# Drimp_Quadcopter.net
KiCad netlist of a schematic drawn in Altium Designer
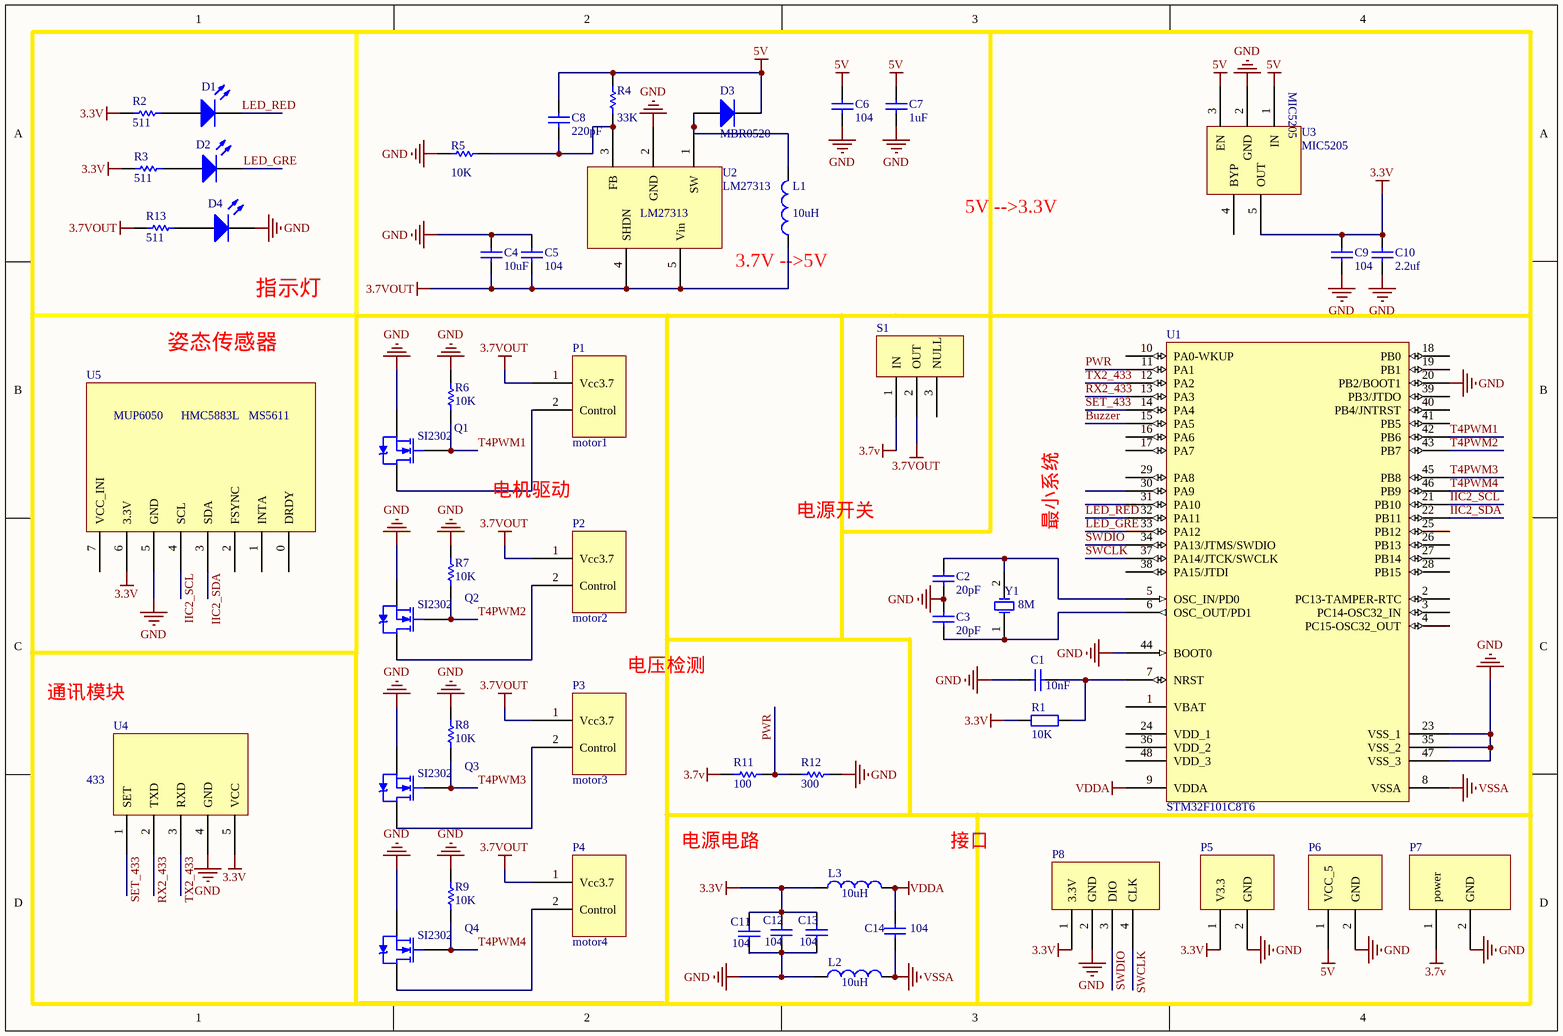
[diagram p0: Drimp_Quadcopter_升压部分未改变.SchDoc]

(export (version "E")
  (design (tool "Eeschema 10.0.6"))
  (components
    (comp (ref "C1")
      (value "10nF")
      (footprint "0603-N-CAP")
      (description "Capacitor")
      (fields (field (name "Comment") "Cap") (field (name "PUBLISHER") "Altium Limited"))
      (libsource (lib "Miscellaneous Devices") (part "Cap"))
    )
    (comp (ref "C2")
      (value "20pF")
      (footprint "0603-N-CAP")
      (description "Capacitor")
      (fields (field (name "Comment") "Cap") (field (name "PUBLISHER") "Altium Limited"))
      (libsource (lib "Miscellaneous Devices") (part "Cap"))
    )
    (comp (ref "C3")
      (value "20pF")
      (footprint "0603-N-CAP")
      (description "Capacitor")
      (fields (field (name "Comment") "Cap") (field (name "PUBLISHER") "Altium Limited"))
      (libsource (lib "Miscellaneous Devices") (part "Cap"))
    )
    (comp (ref "C4")
      (value "10uF")
      (footprint "0603-N-CAP")
      (description "Capacitor")
      (fields (field (name "Comment") "Cap") (field (name "PUBLISHER") "Altium Limited"))
      (libsource (lib "Miscellaneous Devices") (part "Cap"))
    )
    (comp (ref "C5")
      (value "104")
      (footprint "0603-N-CAP")
      (description "Capacitor")
      (fields (field (name "Comment") "Cap") (field (name "PUBLISHER") "Altium Limited"))
      (libsource (lib "Miscellaneous Devices") (part "Cap"))
    )
    (comp (ref "C6")
      (value "104")
      (footprint "0603-N-CAP")
      (description "Capacitor")
      (fields (field (name "Comment") "Cap") (field (name "PUBLISHER") "Altium Limited"))
      (libsource (lib "Miscellaneous Devices") (part "Cap"))
    )
    (comp (ref "C7")
      (value "1uF")
      (footprint "0603-N-CAP")
      (description "Capacitor")
      (fields (field (name "Comment") "Cap") (field (name "PUBLISHER") "Altium Limited"))
      (libsource (lib "Miscellaneous Devices") (part "Cap"))
    )
    (comp (ref "C8")
      (value "220pF")
      (footprint "0603-N-CAP")
      (description "Capacitor")
      (fields (field (name "Comment") "Cap") (field (name "PUBLISHER") "Altium Limited"))
      (libsource (lib "Miscellaneous Devices") (part "Cap"))
    )
    (comp (ref "C9")
      (value "104")
      (footprint "0603-N-CAP")
      (description "Capacitor")
      (fields (field (name "Comment") "Cap") (field (name "PUBLISHER") "Altium Limited"))
      (libsource (lib "Miscellaneous Devices") (part "Cap"))
    )
    (comp (ref "C10")
      (value "2.2uf")
      (footprint "0603-N-CAP")
      (description "Capacitor")
      (fields (field (name "Comment") "Cap") (field (name "PUBLISHER") "Altium Limited"))
      (libsource (lib "Miscellaneous Devices") (part "Cap"))
    )
    (comp (ref "C11")
      (value "104")
      (footprint "0603-N-CAP")
      (description "Capacitor")
      (fields (field (name "Comment") "Cap") (field (name "PUBLISHER") "Altium Limited"))
      (libsource (lib "Miscellaneous Devices") (part "Cap"))
    )
    (comp (ref "C12")
      (value "104")
      (footprint "0603-N-CAP")
      (description "Capacitor")
      (fields (field (name "Comment") "Cap") (field (name "PUBLISHER") "Altium Limited"))
      (libsource (lib "Miscellaneous Devices") (part "Cap"))
    )
    (comp (ref "C13")
      (value "104")
      (footprint "0603-N-CAP")
      (description "Capacitor")
      (fields (field (name "Comment") "Cap") (field (name "PUBLISHER") "Altium Limited"))
      (libsource (lib "Miscellaneous Devices") (part "Cap"))
    )
    (comp (ref "C14")
      (value "104")
      (footprint "0603-N-CAP")
      (description "Capacitor")
      (fields (field (name "Comment") "Cap") (field (name "PUBLISHER") "Altium Limited"))
      (libsource (lib "Miscellaneous Devices") (part "Cap"))
    )
    (comp (ref "D1")
      (value "D2")
      (footprint "6-0805_N")
      (description "Typical BLUE SiC LED")
      (fields (field (name "PUBLISHER") "Altium Limited"))
      (libsource (lib "Miscellaneous Devices") (part "LED3"))
    )
    (comp (ref "D2")
      (value "D2")
      (footprint "6-0805_N")
      (description "Typical BLUE SiC LED")
      (fields (field (name "PUBLISHER") "Altium Limited"))
      (libsource (lib "Miscellaneous Devices") (part "LED3"))
    )
    (comp (ref "D3")
      (value "MBR0520")
      (footprint "425")
      (description "Default Diode")
      (fields (field (name "PUBLISHER") "Altium Limited"))
      (libsource (lib "Miscellaneous Devices") (part "Diode"))
    )
    (comp (ref "D4")
      (value "D2")
      (footprint "6-0805_N")
      (description "Typical BLUE SiC LED")
      (fields (field (name "PUBLISHER") "Altium Limited"))
      (libsource (lib "Miscellaneous Devices") (part "LED3"))
    )
    (comp (ref "L1")
      (value "10uH")
      (footprint "0603-N - res")
      (description "Inductor")
      (fields (field (name "PUBLISHER") "Altium Limited"))
      (libsource (lib "Miscellaneous Devices") (part "Inductor"))
    )
    (comp (ref "L2")
      (value "10uH")
      (footprint "0603-N - res")
      (description "Inductor")
      (fields (field (name "PUBLISHER") "Altium Limited"))
      (libsource (lib "Miscellaneous Devices") (part "Inductor"))
    )
    (comp (ref "L3")
      (value "10uH")
      (footprint "0603-N - res")
      (description "Inductor")
      (fields (field (name "PUBLISHER") "Altium Limited"))
      (libsource (lib "Miscellaneous Devices") (part "Inductor"))
    )
    (comp (ref "P1")
      (value "motor1")
      (footprint "Motor")
      (description "电机连接口")
      (libsource (lib "Schlib1") (part "motor"))
    )
    (comp (ref "P2")
      (value "motor2")
      (footprint "Motor")
      (description "电机连接口")
      (libsource (lib "Schlib1") (part "motor"))
    )
    (comp (ref "P3")
      (value "motor3")
      (footprint "Motor")
      (description "电机连接口")
      (libsource (lib "Schlib1") (part "motor"))
    )
    (comp (ref "P4")
      (value "motor4")
      (footprint "Motor")
      (description "电机连接口")
      (libsource (lib "Schlib1") (part "motor"))
    )
    (comp (ref "P5") (value "3.3V_GND") (footprint "3.3V_GND") (libsource (lib "Schlib1") (part "3.3V_GND")))
    (comp (ref "P6") (value "5V_GND") (footprint "5V_GND") (libsource (lib "Schlib1") (part "5V_GND")))
    (comp (ref "P7")
      (value "Power_GND")
      (footprint "Power_GND")
      (libsource (lib "Schlib1") (part "Power_GND"))
    )
    (comp (ref "P8")
      (value "SW_download")
      (footprint "SW_download")
      (libsource (lib "Schlib1") (part "SW_download"))
    )
    (comp (ref "Q1")
      (value "SI2302")
      (footprint "SOT-23_M")
      (description "HEXFET Power MOSFET")
      (fields (field (name "PUBLISHER") "Altium Limited"))
      (libsource (lib "IR Discrete MOSFET - Power") (part "IRLML2402"))
    )
    (comp (ref "Q2")
      (value "SI2302")
      (footprint "SOT-23_M")
      (description "HEXFET Power MOSFET")
      (fields (field (name "PUBLISHER") "Altium Limited"))
      (libsource (lib "IR Discrete MOSFET - Power") (part "IRLML2402"))
    )
    (comp (ref "Q3")
      (value "SI2302")
      (footprint "SOT-23_M")
      (description "HEXFET Power MOSFET")
      (fields (field (name "PUBLISHER") "Altium Limited"))
      (libsource (lib "IR Discrete MOSFET - Power") (part "IRLML2402"))
    )
    (comp (ref "Q4")
      (value "SI2302")
      (footprint "SOT-23_M")
      (description "HEXFET Power MOSFET")
      (fields (field (name "PUBLISHER") "Altium Limited"))
      (libsource (lib "IR Discrete MOSFET - Power") (part "IRLML2402"))
    )
    (comp (ref "R1")
      (value "10K")
      (footprint "0603-N - res")
      (description "Resistor")
      (fields (field (name "Comment") "Res2") (field (name "PUBLISHER") "Altium Limited"))
      (libsource (lib "Miscellaneous Devices") (part "Res2"))
    )
    (comp (ref "R2")
      (value "511")
      (footprint "0603-N - res")
      (description "Resistor")
      (fields (field (name "Comment") "Res1") (field (name "PUBLISHER") "Altium Limited"))
      (libsource (lib "Miscellaneous Devices") (part "Res1"))
    )
    (comp (ref "R3")
      (value "511")
      (footprint "0603-N - res")
      (description "Resistor")
      (fields (field (name "Comment") "Res1") (field (name "PUBLISHER") "Altium Limited"))
      (libsource (lib "Miscellaneous Devices") (part "Res1"))
    )
    (comp (ref "R4")
      (value "33K")
      (footprint "0603-N - res")
      (description "Resistor")
      (fields (field (name "Comment") "Res1") (field (name "PUBLISHER") "Altium Limited"))
      (libsource (lib "Miscellaneous Devices") (part "Res1"))
    )
    (comp (ref "R5")
      (value "10K")
      (footprint "0603-N - res")
      (description "Resistor")
      (fields (field (name "Comment") "Res1") (field (name "PUBLISHER") "Altium Limited"))
      (libsource (lib "Miscellaneous Devices") (part "Res1"))
    )
    (comp (ref "R6")
      (value "10K")
      (footprint "0603-N - res")
      (description "Resistor")
      (fields (field (name "Comment") "Res1") (field (name "PUBLISHER") "Altium Limited"))
      (libsource (lib "Miscellaneous Devices") (part "Res1"))
    )
    (comp (ref "R7")
      (value "10K")
      (footprint "0603-N - res")
      (description "Resistor")
      (fields (field (name "Comment") "Res1") (field (name "PUBLISHER") "Altium Limited"))
      (libsource (lib "Miscellaneous Devices") (part "Res1"))
    )
    (comp (ref "R8")
      (value "10K")
      (footprint "0603-N - res")
      (description "Resistor")
      (fields (field (name "Comment") "Res1") (field (name "PUBLISHER") "Altium Limited"))
      (libsource (lib "Miscellaneous Devices") (part "Res1"))
    )
    (comp (ref "R9")
      (value "10K")
      (footprint "0603-N - res")
      (description "Resistor")
      (fields (field (name "Comment") "Res1") (field (name "PUBLISHER") "Altium Limited"))
      (libsource (lib "Miscellaneous Devices") (part "Res1"))
    )
    (comp (ref "R11")
      (value "100")
      (footprint "0603-N - res")
      (description "Resistor")
      (fields (field (name "Comment") "Res1") (field (name "PUBLISHER") "Altium Limited"))
      (libsource (lib "Miscellaneous Devices") (part "Res1"))
    )
    (comp (ref "R12")
      (value "300")
      (footprint "0603-N - res")
      (description "Resistor")
      (fields (field (name "Comment") "Res1") (field (name "PUBLISHER") "Altium Limited"))
      (libsource (lib "Miscellaneous Devices") (part "Res1"))
    )
    (comp (ref "R13")
      (value "511")
      (footprint "0603-N - res")
      (description "Resistor")
      (fields (field (name "Comment") "Res1") (field (name "PUBLISHER") "Altium Limited"))
      (libsource (lib "Miscellaneous Devices") (part "Res1"))
    )
    (comp (ref "S1") (value "switch") (footprint "SWITCH") (libsource (lib "Schlib1") (part "switch")))
    (comp (ref "U1")
      (value "STM32F101C8T6")
      (footprint "LQFP48_N")
      (description "STM32 ARM-based 32-bit MCU with 64 Kbytes Flash, 48-pin LQFP, Industrial Temperature")
      (fields (field (name "PUBLISHER") "Altium Limited"))
      (libsource (lib "ST Microcontroller 32-Bit STM32") (part "STM32F101C8T6"))
    )
    (comp (ref "U2")
      (value "LM27313")
      (footprint "SOT-23_5-001")
      (description "3.7V升压到5v")
      (libsource (lib "Schlib1") (part "LM27313"))
    )
    (comp (ref "U3")
      (value "MIC5205")
      (footprint "SOT-23_5-001")
      (description "5V降压到3.3V")
      (libsource (lib "Schlib1") (part "MIC5205"))
    )
    (comp (ref "U4")
      (value "433")
      (footprint "433")
      (description "通讯模块")
      (libsource (lib "Schlib1") (part "433"))
    )
    (comp (ref "U5")
      (value "MPU6050_10")
      (footprint "MPU6050_10")
      (description "MPU6050_10轴")
      (libsource (lib "Schlib1") (part "MPU6050"))
    )
    (comp (ref "Y1")
      (value "8M")
      (footprint "5032_")
      (description "Crystal Oscillator")
      (fields (field (name "PUBLISHER") "Altium Limited"))
      (libsource (lib "Miscellaneous Devices") (part "XTAL"))
    )
  )
  (nets
    (net (code "1") (name "/Buzzer") (class "Default")
      (node (ref "U1") (pin "15") (pinfunction "PA5_15") (pintype "bidirectional"))
    )
    (net (code "2") (name "/IIC2_SCL") (class "Default")
      (node (ref "U1") (pin "21") (pinfunction "PB10_21") (pintype "bidirectional"))
      (node (ref "U5") (pin "4") (pinfunction "SCL_4") (pintype "passive"))
    )
    (net (code "3") (name "/IIC2_SDA") (class "Default")
      (node (ref "U1") (pin "22") (pinfunction "PB11_22") (pintype "bidirectional"))
      (node (ref "U5") (pin "3") (pinfunction "SDA_3") (pintype "passive"))
    )
    (net (code "4") (name "/LED_GRE") (class "Default")
      (node (ref "D2") (pin "2") (pinfunction "K_2") (pintype "passive"))
      (node (ref "U1") (pin "33") (pinfunction "PA12_33") (pintype "bidirectional"))
    )
    (net (code "5") (name "/LED_RED") (class "Default")
      (node (ref "D1") (pin "2") (pinfunction "K_2") (pintype "passive"))
      (node (ref "U1") (pin "32") (pinfunction "PA11_32") (pintype "bidirectional"))
    )
    (net (code "6") (name "/PWR") (class "Default")
      (node (ref "R11") (pin "2") (pinfunction "2_2") (pintype "passive"))
      (node (ref "R12") (pin "1") (pinfunction "1_1") (pintype "passive"))
      (node (ref "U1") (pin "11") (pinfunction "PA1_11") (pintype "bidirectional"))
    )
    (net (code "7") (name "/RX2_433") (class "Default")
      (node (ref "U1") (pin "13") (pinfunction "PA3_13") (pintype "bidirectional"))
      (node (ref "U4") (pin "2") (pinfunction "TXD_2") (pintype "passive"))
    )
    (net (code "8") (name "/SET_433") (class "Default")
      (node (ref "U1") (pin "14") (pinfunction "PA4_14") (pintype "bidirectional"))
      (node (ref "U4") (pin "1") (pinfunction "SET_1") (pintype "passive"))
    )
    (net (code "9") (name "/SWCLK") (class "Default")
      (node (ref "P8") (pin "4") (pinfunction "CLK_4") (pintype "passive"))
      (node (ref "U1") (pin "37") (pinfunction "PA14/JTCK/SWCLK_37") (pintype "bidirectional"))
    )
    (net (code "10") (name "/SWDIO") (class "Default")
      (node (ref "P8") (pin "3") (pinfunction "DIO_3") (pintype "passive"))
      (node (ref "U1") (pin "34") (pinfunction "PA13/JTMS/SWDIO_34") (pintype "bidirectional"))
    )
    (net (code "11") (name "/T4PWM1") (class "Default")
      (node (ref "Q1") (pin "1") (pinfunction "G_1") (pintype "passive"))
      (node (ref "R6") (pin "2") (pinfunction "2_2") (pintype "passive"))
      (node (ref "U1") (pin "42") (pinfunction "PB6_42") (pintype "bidirectional"))
    )
    (net (code "12") (name "/T4PWM2") (class "Default")
      (node (ref "Q2") (pin "1") (pinfunction "G_1") (pintype "passive"))
      (node (ref "R7") (pin "2") (pinfunction "2_2") (pintype "passive"))
      (node (ref "U1") (pin "43") (pinfunction "PB7_43") (pintype "bidirectional"))
    )
    (net (code "13") (name "/T4PWM3") (class "Default")
      (node (ref "Q3") (pin "1") (pinfunction "G_1") (pintype "passive"))
      (node (ref "R8") (pin "2") (pinfunction "2_2") (pintype "passive"))
      (node (ref "U1") (pin "45") (pinfunction "PB8_45") (pintype "bidirectional"))
    )
    (net (code "14") (name "/T4PWM4") (class "Default")
      (node (ref "Q4") (pin "1") (pinfunction "G_1") (pintype "passive"))
      (node (ref "R9") (pin "2") (pinfunction "2_2") (pintype "passive"))
      (node (ref "U1") (pin "46") (pinfunction "PB9_46") (pintype "bidirectional"))
    )
    (net (code "15") (name "/TX2_433") (class "Default")
      (node (ref "U1") (pin "12") (pinfunction "PA2_12") (pintype "bidirectional"))
      (node (ref "U4") (pin "3") (pinfunction "RXD_3") (pintype "passive"))
    )
    (net (code "16") (name "3.3V") (class "Default")
      (node (ref "C10") (pin "2") (pinfunction "2_2") (pintype "passive"))
      (node (ref "C11") (pin "2") (pinfunction "2_2") (pintype "passive"))
      (node (ref "C12") (pin "2") (pinfunction "2_2") (pintype "passive"))
      (node (ref "C13") (pin "2") (pinfunction "2_2") (pintype "passive"))
      (node (ref "C9") (pin "2") (pinfunction "2_2") (pintype "passive"))
      (node (ref "L3") (pin "1") (pinfunction "1_1") (pintype "passive"))
      (node (ref "P5") (pin "1") (pinfunction "V3.3_1") (pintype "passive"))
      (node (ref "P8") (pin "1") (pinfunction "3.3V_1") (pintype "passive"))
      (node (ref "R1") (pin "1") (pinfunction "1_1") (pintype "passive"))
      (node (ref "R2") (pin "2") (pinfunction "2_2") (pintype "passive"))
      (node (ref "R3") (pin "2") (pinfunction "2_2") (pintype "passive"))
      (node (ref "U3") (pin "5") (pinfunction "OUT_5") (pintype "passive"))
      (node (ref "U4") (pin "5") (pinfunction "VCC_5") (pintype "passive"))
      (node (ref "U5") (pin "6") (pinfunction "3.3V_6") (pintype "passive"))
    )
    (net (code "17") (name "3.7VOUT") (class "Default")
      (node (ref "C4") (pin "1") (pinfunction "1_1") (pintype "passive"))
      (node (ref "C5") (pin "1") (pinfunction "1_1") (pintype "passive"))
      (node (ref "L1") (pin "1") (pinfunction "1_1") (pintype "passive"))
      (node (ref "P1") (pin "1") (pinfunction "Vcc3.7_1") (pintype "passive"))
      (node (ref "P2") (pin "1") (pinfunction "Vcc3.7_1") (pintype "passive"))
      (node (ref "P3") (pin "1") (pinfunction "Vcc3.7_1") (pintype "passive"))
      (node (ref "P4") (pin "1") (pinfunction "Vcc3.7_1") (pintype "passive"))
      (node (ref "R13") (pin "2") (pinfunction "2_2") (pintype "passive"))
      (node (ref "S1") (pin "2") (pinfunction "OUT_2") (pintype "passive"))
      (node (ref "U2") (pin "4") (pinfunction "SHDN_4") (pintype "passive"))
      (node (ref "U2") (pin "5") (pinfunction "Vin_5") (pintype "passive"))
    )
    (net (code "18") (name "3.7v") (class "Default")
      (node (ref "P7") (pin "1") (pinfunction "power_1") (pintype "passive"))
      (node (ref "R11") (pin "1") (pinfunction "1_1") (pintype "passive"))
      (node (ref "S1") (pin "1") (pinfunction "IN_1") (pintype "passive"))
    )
    (net (code "19") (name "5V") (class "Default")
      (node (ref "C6") (pin "2") (pinfunction "2_2") (pintype "passive"))
      (node (ref "C7") (pin "2") (pinfunction "2_2") (pintype "passive"))
      (node (ref "C8") (pin "2") (pinfunction "2_2") (pintype "passive"))
      (node (ref "D3") (pin "2") (pinfunction "K_2") (pintype "passive"))
      (node (ref "P6") (pin "1") (pinfunction "VCC_5_1") (pintype "passive"))
      (node (ref "R4") (pin "2") (pinfunction "2_2") (pintype "passive"))
      (node (ref "U3") (pin "1") (pinfunction "IN_1") (pintype "passive"))
      (node (ref "U3") (pin "3") (pinfunction "EN_3") (pintype "passive"))
    )
    (net (code "20") (name "GND") (class "Default")
      (node (ref "C1") (pin "1") (pinfunction "1_1") (pintype "passive"))
      (node (ref "C10") (pin "1") (pinfunction "1_1") (pintype "passive"))
      (node (ref "C11") (pin "1") (pinfunction "1_1") (pintype "passive"))
      (node (ref "C12") (pin "1") (pinfunction "1_1") (pintype "passive"))
      (node (ref "C13") (pin "1") (pinfunction "1_1") (pintype "passive"))
      (node (ref "C2") (pin "1") (pinfunction "1_1") (pintype "passive"))
      (node (ref "C3") (pin "2") (pinfunction "2_2") (pintype "passive"))
      (node (ref "C4") (pin "2") (pinfunction "2_2") (pintype "passive"))
      (node (ref "C5") (pin "2") (pinfunction "2_2") (pintype "passive"))
      (node (ref "C6") (pin "1") (pinfunction "1_1") (pintype "passive"))
      (node (ref "C7") (pin "1") (pinfunction "1_1") (pintype "passive"))
      (node (ref "C9") (pin "1") (pinfunction "1_1") (pintype "passive"))
      (node (ref "D4") (pin "2") (pinfunction "K_2") (pintype "passive"))
      (node (ref "L2") (pin "1") (pinfunction "1_1") (pintype "passive"))
      (node (ref "P5") (pin "2") (pinfunction "GND_2") (pintype "passive"))
      (node (ref "P6") (pin "2") (pinfunction "GND_2") (pintype "passive"))
      (node (ref "P7") (pin "2") (pinfunction "GND_2") (pintype "passive"))
      (node (ref "P8") (pin "2") (pinfunction "GND_2") (pintype "passive"))
      (node (ref "Q1") (pin "2") (pinfunction "S_2") (pintype "passive"))
      (node (ref "Q2") (pin "2") (pinfunction "S_2") (pintype "passive"))
      (node (ref "Q3") (pin "2") (pinfunction "S_2") (pintype "passive"))
      (node (ref "Q4") (pin "2") (pinfunction "S_2") (pintype "passive"))
      (node (ref "R12") (pin "2") (pinfunction "2_2") (pintype "passive"))
      (node (ref "R5") (pin "1") (pinfunction "1_1") (pintype "passive"))
      (node (ref "R6") (pin "1") (pinfunction "1_1") (pintype "passive"))
      (node (ref "R7") (pin "1") (pinfunction "1_1") (pintype "passive"))
      (node (ref "R8") (pin "1") (pinfunction "1_1") (pintype "passive"))
      (node (ref "R9") (pin "1") (pinfunction "1_1") (pintype "passive"))
      (node (ref "U1") (pin "20") (pinfunction "PB2/BOOT1_20") (pintype "bidirectional"))
      (node (ref "U1") (pin "23") (pinfunction "VSS_1_23") (pintype "power_in"))
      (node (ref "U1") (pin "35") (pinfunction "VSS_2_35") (pintype "power_in"))
      (node (ref "U1") (pin "44") (pinfunction "BOOT0_44") (pintype "input"))
      (node (ref "U1") (pin "47") (pinfunction "VSS_3_47") (pintype "power_in"))
      (node (ref "U2") (pin "2") (pinfunction "GND_2") (pintype "passive"))
      (node (ref "U3") (pin "2") (pinfunction "GND_2") (pintype "passive"))
      (node (ref "U4") (pin "4") (pinfunction "GND_4") (pintype "passive"))
      (node (ref "U5") (pin "5") (pinfunction "GND_5") (pintype "passive"))
    )
    (net (code "21") (name "Net-(D1-A)") (class "Default")
      (node (ref "D1") (pin "1") (pinfunction "A_1") (pintype "passive"))
      (node (ref "R2") (pin "1") (pinfunction "1_1") (pintype "passive"))
    )
    (net (code "22") (name "Net-(D2-A)") (class "Default")
      (node (ref "D2") (pin "1") (pinfunction "A_1") (pintype "passive"))
      (node (ref "R3") (pin "1") (pinfunction "1_1") (pintype "passive"))
    )
    (net (code "23") (name "Net-(D3-A)") (class "Default")
      (node (ref "D3") (pin "1") (pinfunction "A_1") (pintype "passive"))
      (node (ref "L1") (pin "2") (pinfunction "2_2") (pintype "passive"))
      (node (ref "U2") (pin "1") (pinfunction "SW_1") (pintype "passive"))
    )
    (net (code "24") (name "Net-(D4-A)") (class "Default")
      (node (ref "D4") (pin "1") (pinfunction "A_1") (pintype "passive"))
      (node (ref "R13") (pin "1") (pinfunction "1_1") (pintype "passive"))
    )
    (net (code "25") (name "Net-(P1-Control)") (class "Default")
      (node (ref "P1") (pin "2") (pinfunction "Control_2") (pintype "passive"))
      (node (ref "Q1") (pin "3") (pinfunction "D_3") (pintype "passive"))
    )
    (net (code "26") (name "Net-(P2-Control)") (class "Default")
      (node (ref "P2") (pin "2") (pinfunction "Control_2") (pintype "passive"))
      (node (ref "Q2") (pin "3") (pinfunction "D_3") (pintype "passive"))
    )
    (net (code "27") (name "Net-(P3-Control)") (class "Default")
      (node (ref "P3") (pin "2") (pinfunction "Control_2") (pintype "passive"))
      (node (ref "Q3") (pin "3") (pinfunction "D_3") (pintype "passive"))
    )
    (net (code "28") (name "Net-(P4-Control)") (class "Default")
      (node (ref "P4") (pin "2") (pinfunction "Control_2") (pintype "passive"))
      (node (ref "Q4") (pin "3") (pinfunction "D_3") (pintype "passive"))
    )
    (net (code "29") (name "Net-(U1-NRST)") (class "Default")
      (node (ref "C1") (pin "2") (pinfunction "2_2") (pintype "passive"))
      (node (ref "R1") (pin "2") (pinfunction "2_2") (pintype "passive"))
      (node (ref "U1") (pin "7") (pinfunction "NRST_7") (pintype "bidirectional"))
    )
    (net (code "30") (name "Net-(U1-OSC_IN{slash}PD0)") (class "Default")
      (node (ref "C2") (pin "2") (pinfunction "2_2") (pintype "passive"))
      (node (ref "U1") (pin "5") (pinfunction "OSC_IN/PD0_5") (pintype "input"))
      (node (ref "Y1") (pin "2") (pinfunction "OSC2_2") (pintype "passive"))
    )
    (net (code "31") (name "Net-(U1-OSC_OUT{slash}PD1)") (class "Default")
      (node (ref "C3") (pin "1") (pinfunction "1_1") (pintype "passive"))
      (node (ref "U1") (pin "6") (pinfunction "OSC_OUT/PD1_6") (pintype "output"))
      (node (ref "Y1") (pin "1") (pinfunction "OSC1_1") (pintype "passive"))
    )
    (net (code "32") (name "Net-(U2-FB)") (class "Default")
      (node (ref "C8") (pin "1") (pinfunction "1_1") (pintype "passive"))
      (node (ref "R4") (pin "1") (pinfunction "1_1") (pintype "passive"))
      (node (ref "R5") (pin "2") (pinfunction "2_2") (pintype "passive"))
      (node (ref "U2") (pin "3") (pinfunction "FB_3") (pintype "passive"))
    )
    (net (code "33") (name "VDDA") (class "Default")
      (node (ref "C14") (pin "2") (pinfunction "2_2") (pintype "passive"))
      (node (ref "L3") (pin "2") (pinfunction "2_2") (pintype "passive"))
      (node (ref "U1") (pin "9") (pinfunction "VDDA_9") (pintype "power_in"))
    )
    (net (code "34") (name "VSSA") (class "Default")
      (node (ref "C14") (pin "1") (pinfunction "1_1") (pintype "passive"))
      (node (ref "L2") (pin "2") (pinfunction "2_2") (pintype "passive"))
      (node (ref "U1") (pin "8") (pinfunction "VSSA_8") (pintype "power_in"))
    )
    (net (code "35") (name "unconnected-(S1-NULL-Pad3)") (class "Default")
      (node (ref "S1") (pin "3") (pinfunction "NULL_3") (pintype "passive"))
    )
    (net (code "36") (name "unconnected-(U1-PA0-WKUP-Pad10)") (class "Default")
      (node (ref "U1") (pin "10") (pinfunction "PA0-WKUP_10") (pintype "bidirectional"))
    )
    (net (code "37") (name "unconnected-(U1-PA6-Pad16)") (class "Default")
      (node (ref "U1") (pin "16") (pinfunction "PA6_16") (pintype "bidirectional"))
    )
    (net (code "38") (name "unconnected-(U1-PA7-Pad17)") (class "Default")
      (node (ref "U1") (pin "17") (pinfunction "PA7_17") (pintype "bidirectional"))
    )
    (net (code "39") (name "unconnected-(U1-PA8-Pad29)") (class "Default")
      (node (ref "U1") (pin "29") (pinfunction "PA8_29") (pintype "bidirectional"))
    )
    (net (code "40") (name "unconnected-(U1-PA9-Pad30)") (class "Default")
      (node (ref "U1") (pin "30") (pinfunction "PA9_30") (pintype "bidirectional"))
    )
    (net (code "41") (name "unconnected-(U1-PA10-Pad31)") (class "Default")
      (node (ref "U1") (pin "31") (pinfunction "PA10_31") (pintype "bidirectional"))
    )
    (net (code "42") (name "unconnected-(U1-PA15{slash}JTDI-Pad38)") (class "Default")
      (node (ref "U1") (pin "38") (pinfunction "PA15/JTDI_38") (pintype "bidirectional"))
    )
    (net (code "43") (name "unconnected-(U1-PB0-Pad18)") (class "Default")
      (node (ref "U1") (pin "18") (pinfunction "PB0_18") (pintype "bidirectional"))
    )
    (net (code "44") (name "unconnected-(U1-PB1-Pad19)") (class "Default")
      (node (ref "U1") (pin "19") (pinfunction "PB1_19") (pintype "bidirectional"))
    )
    (net (code "45") (name "unconnected-(U1-PB3{slash}JTDO-Pad39)") (class "Default")
      (node (ref "U1") (pin "39") (pinfunction "PB3/JTDO_39") (pintype "bidirectional"))
    )
    (net (code "46") (name "unconnected-(U1-PB4{slash}JNTRST-Pad40)") (class "Default")
      (node (ref "U1") (pin "40") (pinfunction "PB4/JNTRST_40") (pintype "bidirectional"))
    )
    (net (code "47") (name "unconnected-(U1-PB5-Pad41)") (class "Default")
      (node (ref "U1") (pin "41") (pinfunction "PB5_41") (pintype "bidirectional"))
    )
    (net (code "48") (name "unconnected-(U1-PB12-Pad25)") (class "Default")
      (node (ref "U1") (pin "25") (pinfunction "PB12_25") (pintype "bidirectional"))
    )
    (net (code "49") (name "unconnected-(U1-PB13-Pad26)") (class "Default")
      (node (ref "U1") (pin "26") (pinfunction "PB13_26") (pintype "bidirectional"))
    )
    (net (code "50") (name "unconnected-(U1-PB14-Pad27)") (class "Default")
      (node (ref "U1") (pin "27") (pinfunction "PB14_27") (pintype "bidirectional"))
    )
    (net (code "51") (name "unconnected-(U1-PB15-Pad28)") (class "Default")
      (node (ref "U1") (pin "28") (pinfunction "PB15_28") (pintype "bidirectional"))
    )
    (net (code "52") (name "unconnected-(U1-PC13-TAMPER-RTC-Pad2)") (class "Default")
      (node (ref "U1") (pin "2") (pinfunction "PC13-TAMPER-RTC_2") (pintype "bidirectional"))
    )
    (net (code "53") (name "unconnected-(U1-PC14-OSC32_IN-Pad3)") (class "Default")
      (node (ref "U1") (pin "3") (pinfunction "PC14-OSC32_IN_3") (pintype "bidirectional"))
    )
    (net (code "54") (name "unconnected-(U1-PC15-OSC32_OUT-Pad4)") (class "Default")
      (node (ref "U1") (pin "4") (pinfunction "PC15-OSC32_OUT_4") (pintype "bidirectional"))
    )
    (net (code "55") (name "unconnected-(U1-VBAT-Pad1)") (class "Default")
      (node (ref "U1") (pin "1") (pinfunction "VBAT_1") (pintype "power_in"))
    )
    (net (code "56") (name "unconnected-(U1-VDD_1-Pad24)") (class "Default")
      (node (ref "U1") (pin "24") (pinfunction "VDD_1_24") (pintype "power_in"))
    )
    (net (code "57") (name "unconnected-(U1-VDD_2-Pad36)") (class "Default")
      (node (ref "U1") (pin "36") (pinfunction "VDD_2_36") (pintype "power_in"))
    )
    (net (code "58") (name "unconnected-(U1-VDD_3-Pad48)") (class "Default")
      (node (ref "U1") (pin "48") (pinfunction "VDD_3_48") (pintype "power_in"))
    )
    (net (code "59") (name "unconnected-(U3-BYP-Pad4)") (class "Default")
      (node (ref "U3") (pin "4") (pinfunction "BYP_4") (pintype "passive"))
    )
    (net (code "60") (name "unconnected-(U5-DRDY-Pad0)") (class "Default")
      (node (ref "U5") (pin "0") (pinfunction "DRDY_0") (pintype "passive"))
    )
    (net (code "61") (name "unconnected-(U5-FSYNC-Pad2)") (class "Default")
      (node (ref "U5") (pin "2") (pinfunction "FSYNC_2") (pintype "passive"))
    )
    (net (code "62") (name "unconnected-(U5-INTA-Pad1)") (class "Default")
      (node (ref "U5") (pin "1") (pinfunction "INTA_1") (pintype "passive"))
    )
    (net (code "63") (name "unconnected-(U5-VCC_INI-Pad7)") (class "Default")
      (node (ref "U5") (pin "7") (pinfunction "VCC_INI_7") (pintype "passive"))
    )
  )
)
